# PocaSeek.net
KiCad netlist of a schematic drawn in EAGLE
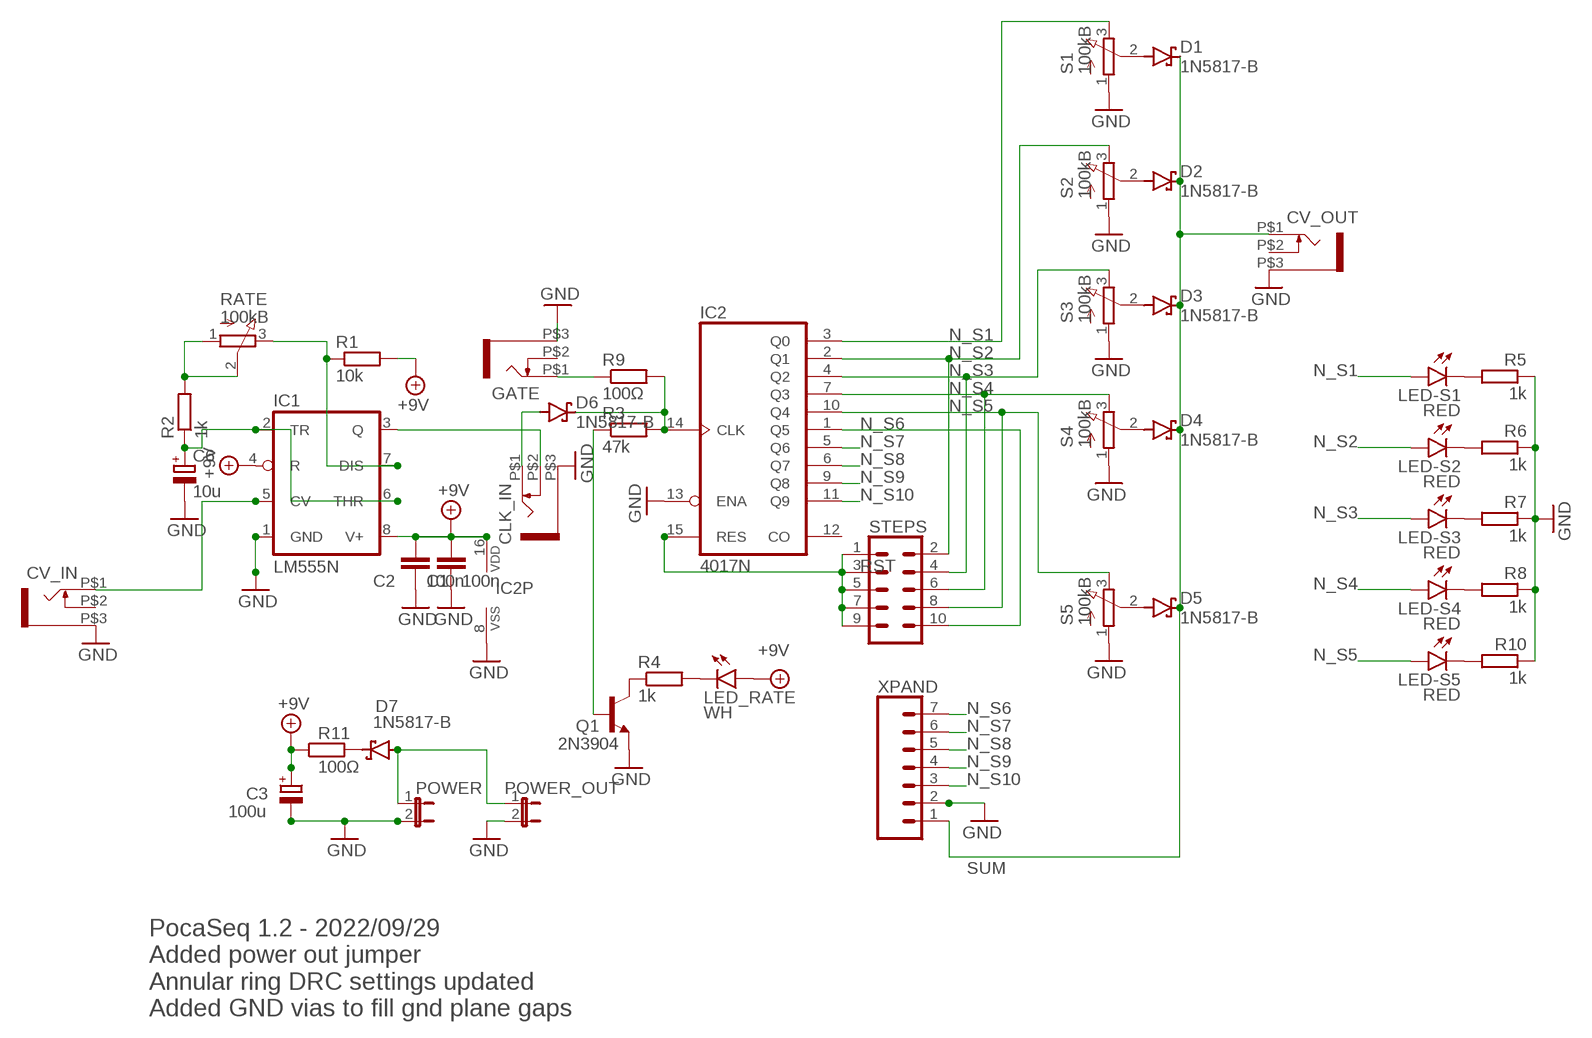
[diagram p0: schematic, sheet 1]

(export (version "E")
  (design (tool "Eeschema 10.0.6"))
  (components
    (comp (ref "C1")
      (value "100n")
      (footprint "eagle-import:C050-024X044")
      (libsource (lib "eagle-import") (part "C-EU050-024X044"))
    )
    (comp (ref "C2")
      (value "100n")
      (footprint "eagle-import:C050-024X044")
      (libsource (lib "eagle-import") (part "C-EU050-024X044"))
    )
    (comp (ref "C3")
      (value "100u")
      (footprint "eagle-import:E2,5-7")
      (libsource (lib "eagle-import") (part "CPOL-EUE2.5-7"))
    )
    (comp (ref "C6")
      (value "10u")
      (footprint "eagle-import:E2,5-6")
      (libsource (lib "eagle-import") (part "CPOL-EUE2.5-6"))
    )
    (comp (ref "CLK_IN")
      (value "WQP-PJ301M-12_JACK")
      (footprint "eagle-import:WQP-PJ301M-12_JACK")
      (libsource (lib "eagle-import") (part "WQP-PJ301M-12_JACK"))
    )
    (comp (ref "CV_IN")
      (value "WQP-PJ301M-12_JACK")
      (footprint "eagle-import:WQP-PJ301M-12_JACK")
      (libsource (lib "eagle-import") (part "WQP-PJ301M-12_JACK"))
    )
    (comp (ref "CV_OUT")
      (value "WQP-PJ301M-12_JACK")
      (footprint "eagle-import:WQP-PJ301M-12_JACK")
      (libsource (lib "eagle-import") (part "WQP-PJ301M-12_JACK"))
    )
    (comp (ref "D1")
      (value "1N5817-B")
      (footprint "eagle-import:DO41-7.6")
      (libsource (lib "eagle-import") (part "1N5817-B"))
    )
    (comp (ref "D2")
      (value "1N5817-B")
      (footprint "eagle-import:DO41-7.6")
      (libsource (lib "eagle-import") (part "1N5817-B"))
    )
    (comp (ref "D3")
      (value "1N5817-B")
      (footprint "eagle-import:DO41-7.6")
      (libsource (lib "eagle-import") (part "1N5817-B"))
    )
    (comp (ref "D4")
      (value "1N5817-B")
      (footprint "eagle-import:DO41-7.6")
      (libsource (lib "eagle-import") (part "1N5817-B"))
    )
    (comp (ref "D5")
      (value "1N5817-B")
      (footprint "eagle-import:DO41-7.6")
      (libsource (lib "eagle-import") (part "1N5817-B"))
    )
    (comp (ref "D6")
      (value "1N5817-B")
      (footprint "eagle-import:DO41-7.6")
      (libsource (lib "eagle-import") (part "1N5817-B"))
    )
    (comp (ref "D7")
      (value "1N5817-B")
      (footprint "eagle-import:DO41-7.6")
      (libsource (lib "eagle-import") (part "1N5817-B"))
    )
    (comp (ref "GATE")
      (value "WQP-PJ301M-12_JACK")
      (footprint "eagle-import:WQP-PJ301M-12_JACK")
      (libsource (lib "eagle-import") (part "WQP-PJ301M-12_JACK"))
    )
    (comp (ref "IC1")
      (value "LM555N")
      (footprint "eagle-import:DIL08")
      (libsource (lib "eagle-import") (part "555NLM"))
    )
    (comp (ref "IC2")
      (value "4017N")
      (footprint "eagle-import:DIL16")
      (libsource (lib "eagle-import") (part "4017N"))
    )
    (comp (ref "LED-S1")
      (value "RED")
      (footprint "eagle-import:LED3MM")
      (libsource (lib "eagle-import") (part "LED3MM"))
    )
    (comp (ref "LED-S2")
      (value "RED")
      (footprint "eagle-import:LED3MM")
      (libsource (lib "eagle-import") (part "LED3MM"))
    )
    (comp (ref "LED-S3")
      (value "RED")
      (footprint "eagle-import:LED3MM")
      (libsource (lib "eagle-import") (part "LED3MM"))
    )
    (comp (ref "LED-S4")
      (value "RED")
      (footprint "eagle-import:LED3MM")
      (libsource (lib "eagle-import") (part "LED3MM"))
    )
    (comp (ref "LED-S5")
      (value "RED")
      (footprint "eagle-import:LED3MM")
      (libsource (lib "eagle-import") (part "LED3MM"))
    )
    (comp (ref "LED_RATE")
      (value "WH")
      (footprint "eagle-import:LED3MM")
      (libsource (lib "eagle-import") (part "LED3MM"))
    )
    (comp (ref "POWER")
      (value "JP1E")
      (footprint "eagle-import:JP1")
      (libsource (lib "eagle-import") (part "JP1E"))
    )
    (comp (ref "POWER_OUT")
      (value "JP1E")
      (footprint "eagle-import:JP1")
      (libsource (lib "eagle-import") (part "JP1E"))
    )
    (comp (ref "Q1")
      (value "2N3904")
      (footprint "eagle-import:TO92")
      (libsource (lib "eagle-import") (part "2N3904"))
    )
    (comp (ref "R1")
      (value "10k")
      (footprint "eagle-import:0204_7")
      (libsource (lib "eagle-import") (part "R-EU_0204/7"))
    )
    (comp (ref "R2")
      (value "1k")
      (footprint "eagle-import:0204_7")
      (libsource (lib "eagle-import") (part "R-EU_0204/7"))
    )
    (comp (ref "R3")
      (value "47k")
      (footprint "eagle-import:0204_7")
      (libsource (lib "eagle-import") (part "R-EU_0204/7"))
    )
    (comp (ref "R4")
      (value "1k")
      (footprint "eagle-import:0204_7")
      (libsource (lib "eagle-import") (part "R-EU_0204/7"))
    )
    (comp (ref "R5")
      (value "1k")
      (footprint "eagle-import:0204V")
      (libsource (lib "eagle-import") (part "R-EU_0204/2V"))
    )
    (comp (ref "R6")
      (value "1k")
      (footprint "eagle-import:0204V")
      (libsource (lib "eagle-import") (part "R-EU_0204/2V"))
    )
    (comp (ref "R7")
      (value "1k")
      (footprint "eagle-import:0204V")
      (libsource (lib "eagle-import") (part "R-EU_0204/2V"))
    )
    (comp (ref "R8")
      (value "1k")
      (footprint "eagle-import:0204V")
      (libsource (lib "eagle-import") (part "R-EU_0204/2V"))
    )
    (comp (ref "R9")
      (value "100Ω")
      (footprint "eagle-import:0204_7")
      (libsource (lib "eagle-import") (part "R-EU_0204/7"))
    )
    (comp (ref "R10")
      (value "1k")
      (footprint "eagle-import:0204V")
      (libsource (lib "eagle-import") (part "R-EU_0204/2V"))
    )
    (comp (ref "R11")
      (value "100Ω")
      (footprint "eagle-import:0204_7")
      (libsource (lib "eagle-import") (part "R-EU_0204/7"))
    )
    (comp (ref "RATE")
      (value "100kB")
      (footprint "eagle-import:EVUFXM")
      (libsource (lib "eagle-import") (part "EVUMF3"))
    )
    (comp (ref "S1")
      (value "100kB")
      (footprint "eagle-import:EVUFXM")
      (libsource (lib "eagle-import") (part "EVUMF3"))
    )
    (comp (ref "S2")
      (value "100kB")
      (footprint "eagle-import:EVUFXM")
      (libsource (lib "eagle-import") (part "EVUMF3"))
    )
    (comp (ref "S3")
      (value "100kB")
      (footprint "eagle-import:EVUFXM")
      (libsource (lib "eagle-import") (part "EVUMF3"))
    )
    (comp (ref "S4")
      (value "100kB")
      (footprint "eagle-import:EVUFXM")
      (libsource (lib "eagle-import") (part "EVUMF3"))
    )
    (comp (ref "S5")
      (value "100kB")
      (footprint "eagle-import:EVUFXM")
      (libsource (lib "eagle-import") (part "EVUMF3"))
    )
    (comp (ref "STEPS")
      (value "CONN_05X2PTH")
      (footprint "eagle-import:2X5")
      (libsource (lib "eagle-import") (part "CONN_05X2PTH"))
    )
    (comp (ref "XPAND")
      (value "CONN_07LOCK")
      (footprint "eagle-import:1X07_LOCK")
      (libsource (lib "eagle-import") (part "CONN_07LOCK"))
    )
  )
  (nets
    (net (code "1") (name "+9V") (class "Default")
      (node (ref "C1") (pin "1") (pinfunction "1_1") (pintype "passive"))
      (node (ref "C2") (pin "1") (pinfunction "1_1") (pintype "passive"))
      (node (ref "C3") (pin "+") (pinfunction "+_+") (pintype "passive"))
      (node (ref "IC1") (pin "4") (pinfunction "R_4") (pintype "input"))
      (node (ref "IC1") (pin "8") (pinfunction "V+_8") (pintype "power_in"))
      (node (ref "IC2") (pin "16") (pinfunction "VDD_16") (pintype "power_in"))
      (node (ref "LED_RATE") (pin "A") (pinfunction "A_A") (pintype "passive"))
      (node (ref "R1") (pin "2") (pinfunction "2_2") (pintype "passive"))
      (node (ref "R11") (pin "1") (pinfunction "1_1") (pintype "passive"))
    )
    (net (code "2") (name "/N_S1") (class "Default")
      (node (ref "IC2") (pin "3") (pinfunction "Q0_3") (pintype "output"))
      (node (ref "LED-S1") (pin "A") (pinfunction "A_A") (pintype "passive"))
      (node (ref "S1") (pin "3") (pinfunction "E_3") (pintype "passive"))
    )
    (net (code "3") (name "/N_S2") (class "Default")
      (node (ref "IC2") (pin "2") (pinfunction "Q1_2") (pintype "output"))
      (node (ref "LED-S2") (pin "A") (pinfunction "A_A") (pintype "passive"))
      (node (ref "S2") (pin "3") (pinfunction "E_3") (pintype "passive"))
      (node (ref "STEPS") (pin "2") (pinfunction "2_2") (pintype "passive"))
    )
    (net (code "4") (name "/N_S3") (class "Default")
      (node (ref "IC2") (pin "4") (pinfunction "Q2_4") (pintype "output"))
      (node (ref "LED-S3") (pin "A") (pinfunction "A_A") (pintype "passive"))
      (node (ref "S3") (pin "3") (pinfunction "E_3") (pintype "passive"))
      (node (ref "STEPS") (pin "4") (pinfunction "4_4") (pintype "passive"))
    )
    (net (code "5") (name "/N_S4") (class "Default")
      (node (ref "IC2") (pin "7") (pinfunction "Q3_7") (pintype "output"))
      (node (ref "LED-S4") (pin "A") (pinfunction "A_A") (pintype "passive"))
      (node (ref "S4") (pin "3") (pinfunction "E_3") (pintype "passive"))
      (node (ref "STEPS") (pin "6") (pinfunction "6_6") (pintype "passive"))
    )
    (net (code "6") (name "/N_S5") (class "Default")
      (node (ref "IC2") (pin "10") (pinfunction "Q4_10") (pintype "output"))
      (node (ref "LED-S5") (pin "A") (pinfunction "A_A") (pintype "passive"))
      (node (ref "S5") (pin "3") (pinfunction "E_3") (pintype "passive"))
      (node (ref "STEPS") (pin "8") (pinfunction "8_8") (pintype "passive"))
    )
    (net (code "7") (name "/N_S6") (class "Default")
      (node (ref "IC2") (pin "1") (pinfunction "Q5_1") (pintype "output"))
      (node (ref "STEPS") (pin "10") (pinfunction "10_10") (pintype "passive"))
      (node (ref "XPAND") (pin "7") (pinfunction "7_7") (pintype "passive"))
    )
    (net (code "8") (name "/N_S7") (class "Default")
      (node (ref "IC2") (pin "5") (pinfunction "Q6_5") (pintype "output"))
      (node (ref "XPAND") (pin "6") (pinfunction "6_6") (pintype "passive"))
    )
    (net (code "9") (name "/N_S8") (class "Default")
      (node (ref "IC2") (pin "6") (pinfunction "Q7_6") (pintype "output"))
      (node (ref "XPAND") (pin "5") (pinfunction "5_5") (pintype "passive"))
    )
    (net (code "10") (name "/N_S9") (class "Default")
      (node (ref "IC2") (pin "9") (pinfunction "Q8_9") (pintype "output"))
      (node (ref "XPAND") (pin "4") (pinfunction "4_4") (pintype "passive"))
    )
    (net (code "11") (name "/N_S10") (class "Default")
      (node (ref "IC2") (pin "11") (pinfunction "Q9_11") (pintype "output"))
      (node (ref "XPAND") (pin "3") (pinfunction "3_3") (pintype "passive"))
    )
    (net (code "12") (name "/RST") (class "Default")
      (node (ref "IC2") (pin "15") (pinfunction "RES_15") (pintype "input"))
      (node (ref "STEPS") (pin "1") (pinfunction "1_1") (pintype "passive"))
      (node (ref "STEPS") (pin "3") (pinfunction "3_3") (pintype "passive"))
      (node (ref "STEPS") (pin "5") (pinfunction "5_5") (pintype "passive"))
      (node (ref "STEPS") (pin "7") (pinfunction "7_7") (pintype "passive"))
      (node (ref "STEPS") (pin "9") (pinfunction "9_9") (pintype "passive"))
    )
    (net (code "13") (name "/SUM") (class "Default")
      (node (ref "CV_OUT") (pin "P$1") (pinfunction "2_P$1") (pintype "passive"))
      (node (ref "D1") (pin "C") (pinfunction "C_C") (pintype "passive"))
      (node (ref "D2") (pin "C") (pinfunction "C_C") (pintype "passive"))
      (node (ref "D3") (pin "C") (pinfunction "C_C") (pintype "passive"))
      (node (ref "D4") (pin "C") (pinfunction "C_C") (pintype "passive"))
      (node (ref "D5") (pin "C") (pinfunction "C_C") (pintype "passive"))
      (node (ref "XPAND") (pin "1") (pinfunction "1_1") (pintype "passive"))
    )
    (net (code "14") (name "GND") (class "Default")
      (node (ref "C1") (pin "2") (pinfunction "2_2") (pintype "passive"))
      (node (ref "C2") (pin "2") (pinfunction "2_2") (pintype "passive"))
      (node (ref "C3") (pin "-") (pinfunction "-_-") (pintype "passive"))
      (node (ref "C6") (pin "-") (pinfunction "-_-") (pintype "passive"))
      (node (ref "CLK_IN") (pin "P$3") (pinfunction "1_P$3") (pintype "passive"))
      (node (ref "CV_IN") (pin "P$3") (pinfunction "1_P$3") (pintype "passive"))
      (node (ref "CV_OUT") (pin "P$3") (pinfunction "1_P$3") (pintype "passive"))
      (node (ref "GATE") (pin "P$3") (pinfunction "1_P$3") (pintype "passive"))
      (node (ref "IC1") (pin "1") (pinfunction "GND_1") (pintype "power_in"))
      (node (ref "IC2") (pin "13") (pinfunction "ENA_13") (pintype "input"))
      (node (ref "IC2") (pin "8") (pinfunction "VSS_8") (pintype "power_in"))
      (node (ref "POWER") (pin "2") (pinfunction "2_2") (pintype "passive"))
      (node (ref "POWER_OUT") (pin "2") (pinfunction "2_2") (pintype "passive"))
      (node (ref "Q1") (pin "3") (pinfunction "E_3") (pintype "passive"))
      (node (ref "R10") (pin "1") (pinfunction "1_1") (pintype "passive"))
      (node (ref "R5") (pin "1") (pinfunction "1_1") (pintype "passive"))
      (node (ref "R6") (pin "1") (pinfunction "1_1") (pintype "passive"))
      (node (ref "R7") (pin "1") (pinfunction "1_1") (pintype "passive"))
      (node (ref "R8") (pin "1") (pinfunction "1_1") (pintype "passive"))
      (node (ref "S1") (pin "1") (pinfunction "A_1") (pintype "passive"))
      (node (ref "S2") (pin "1") (pinfunction "A_1") (pintype "passive"))
      (node (ref "S3") (pin "1") (pinfunction "A_1") (pintype "passive"))
      (node (ref "S4") (pin "1") (pinfunction "A_1") (pintype "passive"))
      (node (ref "S5") (pin "1") (pinfunction "A_1") (pintype "passive"))
      (node (ref "XPAND") (pin "2") (pinfunction "2_2") (pintype "passive"))
    )
    (net (code "15") (name "Net-(CLK_IN-2)") (class "Default")
      (node (ref "CLK_IN") (pin "P$1") (pinfunction "2_P$1") (pintype "passive"))
      (node (ref "D6") (pin "A") (pinfunction "A_A") (pintype "passive"))
    )
    (net (code "16") (name "Net-(CLK_IN-3)") (class "Default")
      (node (ref "CLK_IN") (pin "P$2") (pinfunction "3_P$2") (pintype "passive"))
      (node (ref "IC1") (pin "3") (pinfunction "Q_3") (pintype "output"))
    )
    (net (code "17") (name "Net-(CV_IN-2)") (class "Default")
      (node (ref "CV_IN") (pin "P$1") (pinfunction "2_P$1") (pintype "passive"))
      (node (ref "IC1") (pin "5") (pinfunction "CV_5") (pintype "input"))
    )
    (net (code "18") (name "Net-(D7-PadA)") (class "Default")
      (node (ref "D7") (pin "A") (pinfunction "A_A") (pintype "passive"))
      (node (ref "POWER") (pin "1") (pinfunction "1_1") (pintype "passive"))
      (node (ref "POWER_OUT") (pin "1") (pinfunction "1_1") (pintype "passive"))
    )
    (net (code "19") (name "Net-(D7-PadC)") (class "Default")
      (node (ref "D7") (pin "C") (pinfunction "C_C") (pintype "passive"))
      (node (ref "R11") (pin "2") (pinfunction "2_2") (pintype "passive"))
    )
    (net (code "20") (name "Net-(GATE-2)") (class "Default")
      (node (ref "GATE") (pin "P$1") (pinfunction "2_P$1") (pintype "passive"))
      (node (ref "R9") (pin "1") (pinfunction "1_1") (pintype "passive"))
    )
    (net (code "21") (name "Net-(IC1-DIS)") (class "Default")
      (node (ref "IC1") (pin "7") (pinfunction "DIS_7") (pintype "input"))
      (node (ref "R1") (pin "1") (pinfunction "1_1") (pintype "passive"))
      (node (ref "RATE") (pin "3") (pinfunction "E_3") (pintype "passive"))
    )
    (net (code "22") (name "Net-(IC1-THR)") (class "Default")
      (node (ref "C6") (pin "+") (pinfunction "+_+") (pintype "passive"))
      (node (ref "IC1") (pin "2") (pinfunction "TR_2") (pintype "input"))
      (node (ref "IC1") (pin "6") (pinfunction "THR_6") (pintype "input"))
      (node (ref "R2") (pin "1") (pinfunction "1_1") (pintype "passive"))
    )
    (net (code "23") (name "Net-(IC2A-CLK)") (class "Default")
      (node (ref "D6") (pin "C") (pinfunction "C_C") (pintype "passive"))
      (node (ref "IC2") (pin "14") (pinfunction "CLK_14") (pintype "input"))
      (node (ref "R3") (pin "2") (pinfunction "2_2") (pintype "passive"))
      (node (ref "R9") (pin "2") (pinfunction "2_2") (pintype "passive"))
    )
    (net (code "24") (name "Net-(LED-S1-C)") (class "Default")
      (node (ref "LED-S1") (pin "K") (pinfunction "C_K") (pintype "passive"))
      (node (ref "R5") (pin "2") (pinfunction "2_2") (pintype "passive"))
    )
    (net (code "25") (name "Net-(LED-S2-C)") (class "Default")
      (node (ref "LED-S2") (pin "K") (pinfunction "C_K") (pintype "passive"))
      (node (ref "R6") (pin "2") (pinfunction "2_2") (pintype "passive"))
    )
    (net (code "26") (name "Net-(LED-S3-C)") (class "Default")
      (node (ref "LED-S3") (pin "K") (pinfunction "C_K") (pintype "passive"))
      (node (ref "R7") (pin "2") (pinfunction "2_2") (pintype "passive"))
    )
    (net (code "27") (name "Net-(LED-S4-C)") (class "Default")
      (node (ref "LED-S4") (pin "K") (pinfunction "C_K") (pintype "passive"))
      (node (ref "R8") (pin "2") (pinfunction "2_2") (pintype "passive"))
    )
    (net (code "28") (name "Net-(LED-S5-C)") (class "Default")
      (node (ref "LED-S5") (pin "K") (pinfunction "C_K") (pintype "passive"))
      (node (ref "R10") (pin "2") (pinfunction "2_2") (pintype "passive"))
    )
    (net (code "29") (name "Net-(LED_RATE-C)") (class "Default")
      (node (ref "LED_RATE") (pin "K") (pinfunction "C_K") (pintype "passive"))
      (node (ref "R4") (pin "2") (pinfunction "2_2") (pintype "passive"))
    )
    (net (code "30") (name "Net-(Q1-B)") (class "Default")
      (node (ref "Q1") (pin "2") (pinfunction "B_2") (pintype "passive"))
      (node (ref "R3") (pin "1") (pinfunction "1_1") (pintype "passive"))
    )
    (net (code "31") (name "Net-(Q1-C)") (class "Default")
      (node (ref "Q1") (pin "1") (pinfunction "C_1") (pintype "passive"))
      (node (ref "R4") (pin "1") (pinfunction "1_1") (pintype "passive"))
    )
    (net (code "32") (name "Net-(RATE-A)") (class "Default")
      (node (ref "R2") (pin "2") (pinfunction "2_2") (pintype "passive"))
      (node (ref "RATE") (pin "1") (pinfunction "A_1") (pintype "passive"))
      (node (ref "RATE") (pin "2") (pinfunction "S_2") (pintype "passive"))
    )
    (net (code "33") (name "Net-(S1-S)") (class "Default")
      (node (ref "D1") (pin "A") (pinfunction "A_A") (pintype "passive"))
      (node (ref "S1") (pin "2") (pinfunction "S_2") (pintype "passive"))
    )
    (net (code "34") (name "Net-(S2-S)") (class "Default")
      (node (ref "D2") (pin "A") (pinfunction "A_A") (pintype "passive"))
      (node (ref "S2") (pin "2") (pinfunction "S_2") (pintype "passive"))
    )
    (net (code "35") (name "Net-(S3-S)") (class "Default")
      (node (ref "D3") (pin "A") (pinfunction "A_A") (pintype "passive"))
      (node (ref "S3") (pin "2") (pinfunction "S_2") (pintype "passive"))
    )
    (net (code "36") (name "Net-(S4-S)") (class "Default")
      (node (ref "D4") (pin "A") (pinfunction "A_A") (pintype "passive"))
      (node (ref "S4") (pin "2") (pinfunction "S_2") (pintype "passive"))
    )
    (net (code "37") (name "Net-(S5-S)") (class "Default")
      (node (ref "D5") (pin "A") (pinfunction "A_A") (pintype "passive"))
      (node (ref "S5") (pin "2") (pinfunction "S_2") (pintype "passive"))
    )
    (net (code "38") (name "unconnected-(CV_IN-3-PadP$2)") (class "Default")
      (node (ref "CV_IN") (pin "P$2") (pinfunction "3_P$2") (pintype "passive"))
    )
    (net (code "39") (name "unconnected-(CV_OUT-3-PadP$2)") (class "Default")
      (node (ref "CV_OUT") (pin "P$2") (pinfunction "3_P$2") (pintype "passive"))
    )
    (net (code "40") (name "unconnected-(GATE-3-PadP$2)") (class "Default")
      (node (ref "GATE") (pin "P$2") (pinfunction "3_P$2") (pintype "passive"))
    )
    (net (code "41") (name "unconnected-(IC2A-CO-Pad12)") (class "Default")
      (node (ref "IC2") (pin "12") (pinfunction "CO_12") (pintype "output"))
    )
  )
)
